# solar-fan.net
KiCad netlist of a schematic drawn in EAGLE
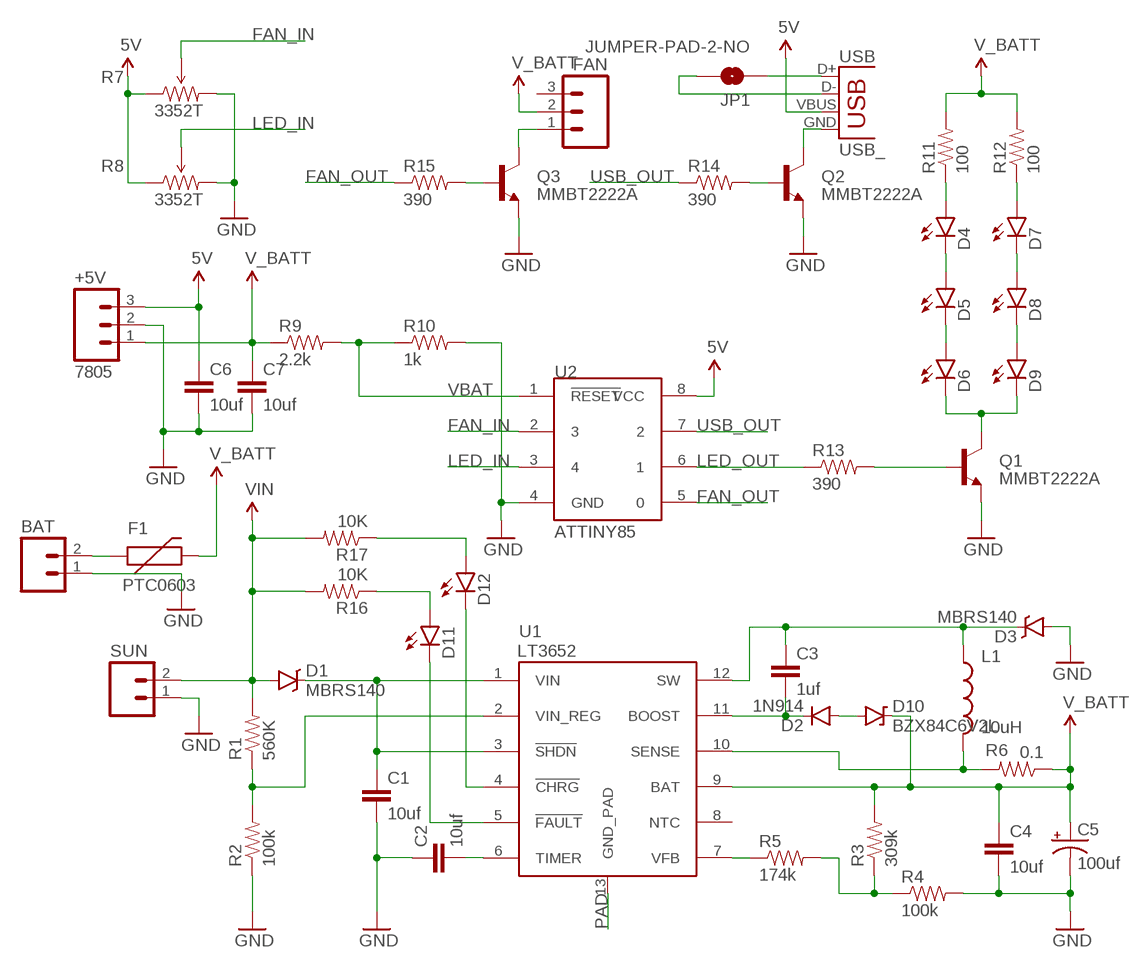
[diagram p0: schematic, sheet 1]

(export (version "E")
  (design (tool "Eeschema 10.0.6"))
  (components
    (comp (ref "+5V")
      (value "7805")
      (footprint "eagle-import:1X03")
      (libsource (lib "eagle-import") (part "M03PTH"))
    )
    (comp (ref "BAT")
      (value "M025MM")
      (footprint "eagle-import:SCREWTERMINAL-5MM-2")
      (libsource (lib "eagle-import") (part "M025MM"))
    )
    (comp (ref "C1")
      (value "10uf")
      (footprint "eagle-import:0603-CAP")
      (libsource (lib "eagle-import") (part "CAP0603-CAP"))
    )
    (comp (ref "C2")
      (value "10uf")
      (footprint "eagle-import:0603-CAP")
      (libsource (lib "eagle-import") (part "CAP0603-CAP"))
    )
    (comp (ref "C3")
      (value "1uf")
      (footprint "eagle-import:0603-CAP")
      (libsource (lib "eagle-import") (part "CAP0603-CAP"))
    )
    (comp (ref "C4")
      (value "10uf")
      (footprint "eagle-import:0603-CAP")
      (libsource (lib "eagle-import") (part "CAP0603-CAP"))
    )
    (comp (ref "C5")
      (value "100uf")
      (footprint "eagle-import:CPOL-RADIAL-100UF-25V")
      (libsource (lib "eagle-import") (part "CAP_POLPTH1"))
    )
    (comp (ref "C6")
      (value "10uf")
      (footprint "eagle-import:0603-CAP")
      (libsource (lib "eagle-import") (part "CAP0603-CAP"))
    )
    (comp (ref "C7")
      (value "10uf")
      (footprint "eagle-import:0603-CAP")
      (libsource (lib "eagle-import") (part "CAP0603-CAP"))
    )
    (comp (ref "D1")
      (value "MBRS140")
      (footprint "eagle-import:SMA-DIODE")
      (libsource (lib "eagle-import") (part "DIODE-SCHOTTKY-MBRA140"))
    )
    (comp (ref "D2")
      (value "1N914")
      (footprint "eagle-import:SOD-323")
      (libsource (lib "eagle-import") (part "DIODEBAS16"))
    )
    (comp (ref "D3")
      (value "MBRS140")
      (footprint "eagle-import:SMA-DIODE")
      (libsource (lib "eagle-import") (part "DIODE-SCHOTTKY-MBRA140"))
    )
    (comp (ref "D4")
      (value "LED-WHITE0603")
      (footprint "eagle-import:LED-0603")
      (libsource (lib "eagle-import") (part "LED-WHITE0603"))
    )
    (comp (ref "D5")
      (value "LED-WHITE0603")
      (footprint "eagle-import:LED-0603")
      (libsource (lib "eagle-import") (part "LED-WHITE0603"))
    )
    (comp (ref "D6")
      (value "LED-WHITE0603")
      (footprint "eagle-import:LED-0603")
      (libsource (lib "eagle-import") (part "LED-WHITE0603"))
    )
    (comp (ref "D7")
      (value "LED-WHITE0603")
      (footprint "eagle-import:LED-0603")
      (libsource (lib "eagle-import") (part "LED-WHITE0603"))
    )
    (comp (ref "D8")
      (value "LED-WHITE0603")
      (footprint "eagle-import:LED-0603")
      (libsource (lib "eagle-import") (part "LED-WHITE0603"))
    )
    (comp (ref "D9")
      (value "LED-WHITE0603")
      (footprint "eagle-import:LED-0603")
      (libsource (lib "eagle-import") (part "LED-WHITE0603"))
    )
    (comp (ref "D10")
      (value "BZX84C6V2L")
      (footprint "eagle-import:SOT23-3")
      (libsource (lib "eagle-import") (part "BZX84C6V2L"))
    )
    (comp (ref "D11")
      (value "LED-WHITE0603")
      (footprint "eagle-import:LED-0603")
      (libsource (lib "eagle-import") (part "LED-WHITE0603"))
    )
    (comp (ref "D12")
      (value "LED-WHITE0603")
      (footprint "eagle-import:LED-0603")
      (libsource (lib "eagle-import") (part "LED-WHITE0603"))
    )
    (comp (ref "F1")
      (value "PTC0603")
      (footprint "eagle-import:0603")
      (libsource (lib "eagle-import") (part "PTC0603"))
    )
    (comp (ref "FAN")
      (value "M03POLAR")
      (footprint "eagle-import:MOLEX-1X3")
      (libsource (lib "eagle-import") (part "M03POLAR"))
    )
    (comp (ref "JP1")
      (value "JUMPER-PAD-2-NO")
      (footprint "eagle-import:PAD-JUMPER-2-NO_NO_SILK")
      (libsource (lib "eagle-import") (part "JUMPER-PAD-2-NO"))
    )
    (comp (ref "L1")
      (value "10uH")
      (footprint "eagle-import:RLB0912")
      (libsource (lib "eagle-import") (part "INDUCTORRLB0912"))
    )
    (comp (ref "Q1")
      (value "MMBT2222A")
      (footprint "eagle-import:SOT23-3")
      (libsource (lib "eagle-import") (part "TRANSISTOR_NPNMMBT2222A"))
    )
    (comp (ref "Q2")
      (value "MMBT2222A")
      (footprint "eagle-import:SOT23-3")
      (libsource (lib "eagle-import") (part "TRANSISTOR_NPNMMBT2222A"))
    )
    (comp (ref "Q3")
      (value "MMBT2222A")
      (footprint "eagle-import:SOT23-3")
      (libsource (lib "eagle-import") (part "TRANSISTOR_NPNMMBT2222A"))
    )
    (comp (ref "R1")
      (value "560K")
      (footprint "eagle-import:0603-RES")
      (libsource (lib "eagle-import") (part "RESISTOR0603-RES"))
    )
    (comp (ref "R2")
      (value "100k")
      (footprint "eagle-import:0603-RES")
      (libsource (lib "eagle-import") (part "RESISTOR0603-RES"))
    )
    (comp (ref "R3")
      (value "309k")
      (footprint "eagle-import:0603-RES")
      (libsource (lib "eagle-import") (part "RESISTOR0603-RES"))
    )
    (comp (ref "R4")
      (value "100k")
      (footprint "eagle-import:0603-RES")
      (libsource (lib "eagle-import") (part "RESISTOR0603-RES"))
    )
    (comp (ref "R5")
      (value "174k")
      (footprint "eagle-import:0603-RES")
      (libsource (lib "eagle-import") (part "RESISTOR0603-RES"))
    )
    (comp (ref "R6")
      (value "0.1")
      (footprint "eagle-import:0603-RES")
      (libsource (lib "eagle-import") (part "RESISTOR0603-RES"))
    )
    (comp (ref "R7")
      (value "3352T")
      (footprint "eagle-import:3352T")
      (libsource (lib "eagle-import") (part "3352T"))
    )
    (comp (ref "R8")
      (value "3352T")
      (footprint "eagle-import:3352T")
      (libsource (lib "eagle-import") (part "3352T"))
    )
    (comp (ref "R9")
      (value "2.2k")
      (footprint "eagle-import:0603-RES")
      (libsource (lib "eagle-import") (part "RESISTOR0603-RES"))
    )
    (comp (ref "R10")
      (value "1k")
      (footprint "eagle-import:0603-RES")
      (libsource (lib "eagle-import") (part "RESISTOR0603-RES"))
    )
    (comp (ref "R11")
      (value "100")
      (footprint "eagle-import:0603-RES")
      (libsource (lib "eagle-import") (part "RESISTOR0603-RES"))
    )
    (comp (ref "R12")
      (value "100")
      (footprint "eagle-import:0603-RES")
      (libsource (lib "eagle-import") (part "RESISTOR0603-RES"))
    )
    (comp (ref "R13")
      (value "390")
      (footprint "eagle-import:0603-RES")
      (libsource (lib "eagle-import") (part "RESISTOR0603-RES"))
    )
    (comp (ref "R14")
      (value "390")
      (footprint "eagle-import:0603-RES")
      (libsource (lib "eagle-import") (part "RESISTOR0603-RES"))
    )
    (comp (ref "R15")
      (value "390")
      (footprint "eagle-import:0603-RES")
      (libsource (lib "eagle-import") (part "RESISTOR0603-RES"))
    )
    (comp (ref "R16")
      (value "10K")
      (footprint "eagle-import:0603-RES")
      (libsource (lib "eagle-import") (part "RESISTOR0603-RES"))
    )
    (comp (ref "R17")
      (value "10K")
      (footprint "eagle-import:0603-RES")
      (libsource (lib "eagle-import") (part "RESISTOR0603-RES"))
    )
    (comp (ref "SUN")
      (value "M025MM")
      (footprint "eagle-import:SCREWTERMINAL-5MM-2")
      (libsource (lib "eagle-import") (part "M025MM"))
    )
    (comp (ref "U1")
      (value "LT3652")
      (footprint "eagle-import:MSOP-12_GND")
      (libsource (lib "eagle-import") (part "LT3652"))
    )
    (comp (ref "U2")
      (value "ATTINY85")
      (footprint "eagle-import:8P3")
      (libsource (lib "eagle-import") (part "ATTINY85"))
    )
    (comp (ref "USB")
      (value "USB_")
      (footprint "eagle-import:USB-A-S-SILK-FEMALE")
      (libsource (lib "eagle-import") (part "USB_"))
    )
  )
  (nets
    (net (code "1") (name "/FAN_IN") (class "Default")
      (node (ref "R7") (pin "WIPER") (pinfunction "WIPER_WIPER") (pintype "passive"))
      (node (ref "U2") (pin "2") (pinfunction "3_2") (pintype "bidirectional"))
    )
    (net (code "2") (name "/FAN_OUT") (class "Default")
      (node (ref "R15") (pin "1") (pinfunction "1_1") (pintype "passive"))
      (node (ref "U2") (pin "5") (pinfunction "0_5") (pintype "bidirectional"))
    )
    (net (code "3") (name "/LED_IN") (class "Default")
      (node (ref "R8") (pin "WIPER") (pinfunction "WIPER_WIPER") (pintype "passive"))
      (node (ref "U2") (pin "3") (pinfunction "4_3") (pintype "bidirectional"))
    )
    (net (code "4") (name "/LED_OUT") (class "Default")
      (node (ref "R13") (pin "1") (pinfunction "1_1") (pintype "passive"))
      (node (ref "U2") (pin "6") (pinfunction "1_6") (pintype "bidirectional"))
    )
    (net (code "5") (name "/PAD") (class "Default")
      (node (ref "U1") (pin "13") (pinfunction "GND_PAD_13") (pintype "bidirectional"))
    )
    (net (code "6") (name "/USB_OUT") (class "Default")
      (node (ref "R14") (pin "1") (pinfunction "1_1") (pintype "passive"))
      (node (ref "U2") (pin "7") (pinfunction "2_7") (pintype "bidirectional"))
    )
    (net (code "7") (name "/VBAT") (class "Default")
      (node (ref "R10") (pin "1") (pinfunction "1_1") (pintype "passive"))
      (node (ref "R9") (pin "2") (pinfunction "2_2") (pintype "passive"))
      (node (ref "U2") (pin "1") (pinfunction "~{RESET}_1") (pintype "bidirectional"))
    )
    (net (code "8") (name "5V") (class "Default")
      (node (ref "+5V") (pin "3") (pinfunction "3_3") (pintype "passive"))
      (node (ref "C6") (pin "1") (pinfunction "1_1") (pintype "passive"))
      (node (ref "R7") (pin "CCW") (pinfunction "CCW_CCW") (pintype "passive"))
      (node (ref "R8") (pin "CCW") (pinfunction "CCW_CCW") (pintype "passive"))
      (node (ref "U2") (pin "8") (pinfunction "VCC_8") (pintype "power_in"))
      (node (ref "USB") (pin "VBUS") (pinfunction "VBUS_VBUS") (pintype "bidirectional"))
    )
    (net (code "9") (name "GND") (class "Default")
      (node (ref "+5V") (pin "2") (pinfunction "2_2") (pintype "passive"))
      (node (ref "BAT") (pin "1") (pinfunction "1_1") (pintype "passive"))
      (node (ref "C1") (pin "2") (pinfunction "2_2") (pintype "passive"))
      (node (ref "C2") (pin "1") (pinfunction "1_1") (pintype "passive"))
      (node (ref "C4") (pin "2") (pinfunction "2_2") (pintype "passive"))
      (node (ref "C5") (pin "2") (pinfunction "-_2") (pintype "passive"))
      (node (ref "C6") (pin "2") (pinfunction "2_2") (pintype "passive"))
      (node (ref "C7") (pin "2") (pinfunction "2_2") (pintype "passive"))
      (node (ref "D3") (pin "A") (pinfunction "A_A") (pintype "passive"))
      (node (ref "Q1") (pin "2") (pinfunction "E_2") (pintype "passive"))
      (node (ref "Q2") (pin "2") (pinfunction "E_2") (pintype "passive"))
      (node (ref "Q3") (pin "2") (pinfunction "E_2") (pintype "passive"))
      (node (ref "R10") (pin "2") (pinfunction "2_2") (pintype "passive"))
      (node (ref "R2") (pin "1") (pinfunction "1_1") (pintype "passive"))
      (node (ref "R4") (pin "2") (pinfunction "2_2") (pintype "passive"))
      (node (ref "R7") (pin "CW") (pinfunction "CW_CW") (pintype "passive"))
      (node (ref "R8") (pin "CW") (pinfunction "CW_CW") (pintype "passive"))
      (node (ref "SUN") (pin "1") (pinfunction "1_1") (pintype "passive"))
      (node (ref "U2") (pin "4") (pinfunction "GND_4") (pintype "power_in"))
    )
    (net (code "10") (name "Net-(BAT-Pad2)") (class "Default")
      (node (ref "BAT") (pin "2") (pinfunction "2_2") (pintype "passive"))
      (node (ref "F1") (pin "1") (pinfunction "1_1") (pintype "bidirectional"))
    )
    (net (code "11") (name "Net-(D4-PadA)") (class "Default")
      (node (ref "D4") (pin "A") (pinfunction "A_A") (pintype "passive"))
      (node (ref "R11") (pin "1") (pinfunction "1_1") (pintype "passive"))
    )
    (net (code "12") (name "Net-(D4-PadC)") (class "Default")
      (node (ref "D4") (pin "C") (pinfunction "C_C") (pintype "passive"))
      (node (ref "D5") (pin "A") (pinfunction "A_A") (pintype "passive"))
    )
    (net (code "13") (name "Net-(D5-PadC)") (class "Default")
      (node (ref "D5") (pin "C") (pinfunction "C_C") (pintype "passive"))
      (node (ref "D6") (pin "A") (pinfunction "A_A") (pintype "passive"))
    )
    (net (code "14") (name "Net-(D7-PadA)") (class "Default")
      (node (ref "D7") (pin "A") (pinfunction "A_A") (pintype "passive"))
      (node (ref "R12") (pin "1") (pinfunction "1_1") (pintype "passive"))
    )
    (net (code "15") (name "Net-(D7-PadC)") (class "Default")
      (node (ref "D7") (pin "C") (pinfunction "C_C") (pintype "passive"))
      (node (ref "D8") (pin "A") (pinfunction "A_A") (pintype "passive"))
    )
    (net (code "16") (name "Net-(D8-PadC)") (class "Default")
      (node (ref "D8") (pin "C") (pinfunction "C_C") (pintype "passive"))
      (node (ref "D9") (pin "A") (pinfunction "A_A") (pintype "passive"))
    )
    (net (code "17") (name "Net-(D10-A)") (class "Default")
      (node (ref "D10") (pin "1") (pinfunction "A_1") (pintype "passive"))
      (node (ref "D2") (pin "A") (pinfunction "A_A") (pintype "passive"))
    )
    (net (code "18") (name "Net-(D11-PadA)") (class "Default")
      (node (ref "D11") (pin "A") (pinfunction "A_A") (pintype "passive"))
      (node (ref "R16") (pin "1") (pinfunction "1_1") (pintype "passive"))
    )
    (net (code "19") (name "Net-(D12-PadA)") (class "Default")
      (node (ref "D12") (pin "A") (pinfunction "A_A") (pintype "passive"))
      (node (ref "R17") (pin "1") (pinfunction "1_1") (pintype "passive"))
    )
    (net (code "20") (name "Net-(JP1-Pad1)") (class "Default")
      (node (ref "JP1") (pin "1") (pinfunction "1_1") (pintype "passive"))
      (node (ref "USB") (pin "D+") (pinfunction "D+_D+") (pintype "bidirectional"))
    )
    (net (code "21") (name "Net-(JP1-Pad2)") (class "Default")
      (node (ref "JP1") (pin "2") (pinfunction "2_2") (pintype "passive"))
      (node (ref "USB") (pin "D-") (pinfunction "D-_D-") (pintype "bidirectional"))
    )
    (net (code "22") (name "Net-(Q1-B)") (class "Default")
      (node (ref "Q1") (pin "1") (pinfunction "B_1") (pintype "passive"))
      (node (ref "R13") (pin "2") (pinfunction "2_2") (pintype "passive"))
    )
    (net (code "23") (name "Net-(Q1-C)") (class "Default")
      (node (ref "D6") (pin "C") (pinfunction "C_C") (pintype "passive"))
      (node (ref "D9") (pin "C") (pinfunction "C_C") (pintype "passive"))
      (node (ref "Q1") (pin "3") (pinfunction "C_3") (pintype "passive"))
    )
    (net (code "24") (name "Net-(Q2-B)") (class "Default")
      (node (ref "Q2") (pin "1") (pinfunction "B_1") (pintype "passive"))
      (node (ref "R14") (pin "2") (pinfunction "2_2") (pintype "passive"))
    )
    (net (code "25") (name "Net-(Q2-C)") (class "Default")
      (node (ref "Q2") (pin "3") (pinfunction "C_3") (pintype "passive"))
      (node (ref "USB") (pin "GND") (pinfunction "GND_GND") (pintype "bidirectional"))
    )
    (net (code "26") (name "Net-(Q3-B)") (class "Default")
      (node (ref "Q3") (pin "1") (pinfunction "B_1") (pintype "passive"))
      (node (ref "R15") (pin "2") (pinfunction "2_2") (pintype "passive"))
    )
    (net (code "27") (name "Net-(Q3-C)") (class "Default")
      (node (ref "FAN") (pin "1") (pinfunction "1_1") (pintype "passive"))
      (node (ref "Q3") (pin "3") (pinfunction "C_3") (pintype "passive"))
    )
    (net (code "28") (name "Net-(R3-Pad1)") (class "Default")
      (node (ref "R3") (pin "1") (pinfunction "1_1") (pintype "passive"))
      (node (ref "R4") (pin "1") (pinfunction "1_1") (pintype "passive"))
      (node (ref "R5") (pin "2") (pinfunction "2_2") (pintype "passive"))
    )
    (net (code "29") (name "Net-(U1-BOOST)") (class "Default")
      (node (ref "C3") (pin "2") (pinfunction "2_2") (pintype "passive"))
      (node (ref "D2") (pin "C") (pinfunction "C_C") (pintype "passive"))
      (node (ref "U1") (pin "11") (pinfunction "BOOST_11") (pintype "bidirectional"))
    )
    (net (code "30") (name "Net-(U1-SENSE)") (class "Default")
      (node (ref "L1") (pin "2") (pinfunction "2_2") (pintype "passive"))
      (node (ref "R6") (pin "2") (pinfunction "2_2") (pintype "passive"))
      (node (ref "U1") (pin "10") (pinfunction "SENSE_10") (pintype "bidirectional"))
    )
    (net (code "31") (name "Net-(U1-SW)") (class "Default")
      (node (ref "C3") (pin "1") (pinfunction "1_1") (pintype "passive"))
      (node (ref "D3") (pin "C") (pinfunction "C_C") (pintype "passive"))
      (node (ref "L1") (pin "1") (pinfunction "1_1") (pintype "passive"))
      (node (ref "U1") (pin "12") (pinfunction "SW_12") (pintype "bidirectional"))
    )
    (net (code "32") (name "Net-(U1-TIMER)") (class "Default")
      (node (ref "C2") (pin "2") (pinfunction "2_2") (pintype "passive"))
      (node (ref "U1") (pin "6") (pinfunction "TIMER_6") (pintype "bidirectional"))
    )
    (net (code "33") (name "Net-(U1-VFB)") (class "Default")
      (node (ref "R5") (pin "1") (pinfunction "1_1") (pintype "passive"))
      (node (ref "U1") (pin "7") (pinfunction "VFB_7") (pintype "bidirectional"))
    )
    (net (code "34") (name "Net-(U1-VIN)") (class "Default")
      (node (ref "C1") (pin "1") (pinfunction "1_1") (pintype "passive"))
      (node (ref "D1") (pin "C") (pinfunction "C_C") (pintype "passive"))
      (node (ref "U1") (pin "1") (pinfunction "VIN_1") (pintype "bidirectional"))
      (node (ref "U1") (pin "3") (pinfunction "~{SHDN}_3") (pintype "bidirectional"))
    )
    (net (code "35") (name "Net-(U1-VIN_REG)") (class "Default")
      (node (ref "R1") (pin "1") (pinfunction "1_1") (pintype "passive"))
      (node (ref "R2") (pin "2") (pinfunction "2_2") (pintype "passive"))
      (node (ref "U1") (pin "2") (pinfunction "VIN_REG_2") (pintype "bidirectional"))
    )
    (net (code "36") (name "Net-(U1-~{CHRG})") (class "Default")
      (node (ref "D12") (pin "C") (pinfunction "C_C") (pintype "passive"))
      (node (ref "U1") (pin "4") (pinfunction "~{CHRG}_4") (pintype "bidirectional"))
    )
    (net (code "37") (name "Net-(U1-~{FAULT})") (class "Default")
      (node (ref "D11") (pin "C") (pinfunction "C_C") (pintype "passive"))
      (node (ref "U1") (pin "5") (pinfunction "~{FAULT}_5") (pintype "bidirectional"))
    )
    (net (code "38") (name "VIN") (class "Default")
      (node (ref "D1") (pin "A") (pinfunction "A_A") (pintype "passive"))
      (node (ref "R1") (pin "2") (pinfunction "2_2") (pintype "passive"))
      (node (ref "R16") (pin "2") (pinfunction "2_2") (pintype "passive"))
      (node (ref "R17") (pin "2") (pinfunction "2_2") (pintype "passive"))
      (node (ref "SUN") (pin "2") (pinfunction "2_2") (pintype "passive"))
    )
    (net (code "39") (name "V_BATT") (class "Default")
      (node (ref "+5V") (pin "1") (pinfunction "1_1") (pintype "passive"))
      (node (ref "C4") (pin "1") (pinfunction "1_1") (pintype "passive"))
      (node (ref "C5") (pin "1") (pinfunction "+_1") (pintype "passive"))
      (node (ref "C7") (pin "1") (pinfunction "1_1") (pintype "passive"))
      (node (ref "D10") (pin "3") (pinfunction "C_3") (pintype "passive"))
      (node (ref "F1") (pin "2") (pinfunction "2_2") (pintype "bidirectional"))
      (node (ref "FAN") (pin "2") (pinfunction "2_2") (pintype "passive"))
      (node (ref "R11") (pin "2") (pinfunction "2_2") (pintype "passive"))
      (node (ref "R12") (pin "2") (pinfunction "2_2") (pintype "passive"))
      (node (ref "R3") (pin "2") (pinfunction "2_2") (pintype "passive"))
      (node (ref "R6") (pin "1") (pinfunction "1_1") (pintype "passive"))
      (node (ref "R9") (pin "1") (pinfunction "1_1") (pintype "passive"))
      (node (ref "U1") (pin "9") (pinfunction "BAT_9") (pintype "bidirectional"))
    )
    (net (code "40") (name "unconnected-(FAN-Pad3)") (class "Default")
      (node (ref "FAN") (pin "3") (pinfunction "3_3") (pintype "passive"))
    )
    (net (code "41") (name "unconnected-(U1-NTC-Pad8)") (class "Default")
      (node (ref "U1") (pin "8") (pinfunction "NTC_8") (pintype "bidirectional"))
    )
  )
)
